# pmod-level-conv.net
KiCad netlist of a schematic drawn in EAGLE
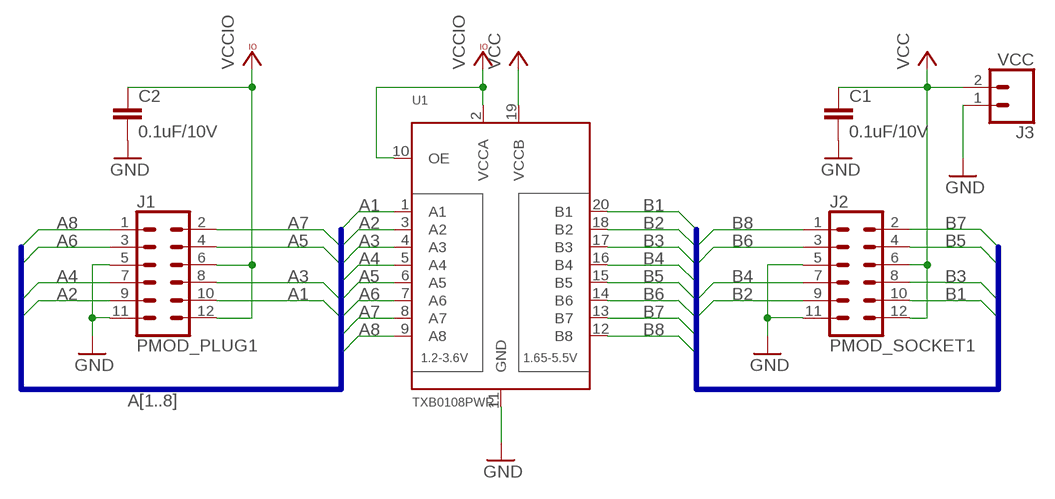
[diagram p0: schematic, sheet 1]

(export (version "E")
  (design (tool "Eeschema 10.0.6"))
  (components
    (comp (ref "C1")
      (value "0.1uF/10V")
      (footprint "eagle-import:C0603K")
      (libsource (lib "eagle-import") (part "C-EUC0603K"))
    )
    (comp (ref "C2")
      (value "0.1uF/10V")
      (footprint "eagle-import:C0603K")
      (libsource (lib "eagle-import") (part "C-EUC0603K"))
    )
    (comp (ref "J1")
      (value "PMOD_PLUG1")
      (footprint "eagle-import:2X6_SMD_RA_PLUG")
      (libsource (lib "eagle-import") (part "CONN_06X2SMD_RA_PLUG"))
    )
    (comp (ref "J2")
      (value "PMOD_SOCKET1")
      (footprint "eagle-import:2X6_SMD_RA_SOCKET")
      (libsource (lib "eagle-import") (part "CONN_06X2SMD_RA_SOCKET"))
    )
    (comp (ref "J3")
      (value "VCC")
      (footprint "eagle-import:JST-2-SMD")
      (libsource (lib "eagle-import") (part "CONN_02-JST-2MM-SMT"))
    )
    (comp (ref "U1")
      (value "TXB0108PWR")
      (footprint "eagle-import:TSSOP20")
      (libsource (lib "eagle-import") (part "TXB0108PWR"))
    )
  )
  (nets
    (net (code "1") (name "/A1") (class "Default")
      (node (ref "J1") (pin "10") (pinfunction "10_10") (pintype "passive"))
      (node (ref "U1") (pin "1") (pinfunction "A1_1") (pintype "bidirectional"))
    )
    (net (code "2") (name "/A2") (class "Default")
      (node (ref "J1") (pin "9") (pinfunction "9_9") (pintype "passive"))
      (node (ref "U1") (pin "3") (pinfunction "A2_3") (pintype "bidirectional"))
    )
    (net (code "3") (name "/A3") (class "Default")
      (node (ref "J1") (pin "8") (pinfunction "8_8") (pintype "passive"))
      (node (ref "U1") (pin "4") (pinfunction "A3_4") (pintype "bidirectional"))
    )
    (net (code "4") (name "/A4") (class "Default")
      (node (ref "J1") (pin "7") (pinfunction "7_7") (pintype "passive"))
      (node (ref "U1") (pin "5") (pinfunction "A4_5") (pintype "bidirectional"))
    )
    (net (code "5") (name "/A5") (class "Default")
      (node (ref "J1") (pin "4") (pinfunction "4_4") (pintype "passive"))
      (node (ref "U1") (pin "6") (pinfunction "A5_6") (pintype "bidirectional"))
    )
    (net (code "6") (name "/A6") (class "Default")
      (node (ref "J1") (pin "3") (pinfunction "3_3") (pintype "passive"))
      (node (ref "U1") (pin "7") (pinfunction "A6_7") (pintype "bidirectional"))
    )
    (net (code "7") (name "/A7") (class "Default")
      (node (ref "J1") (pin "2") (pinfunction "2_2") (pintype "passive"))
      (node (ref "U1") (pin "8") (pinfunction "A7_8") (pintype "bidirectional"))
    )
    (net (code "8") (name "/A8") (class "Default")
      (node (ref "J1") (pin "1") (pinfunction "1_1") (pintype "passive"))
      (node (ref "U1") (pin "9") (pinfunction "A8_9") (pintype "bidirectional"))
    )
    (net (code "10") (name "/B1") (class "Default")
      (node (ref "J2") (pin "10") (pinfunction "10_10") (pintype "passive"))
      (node (ref "U1") (pin "20") (pinfunction "B1_20") (pintype "bidirectional"))
    )
    (net (code "11") (name "/B2") (class "Default")
      (node (ref "J2") (pin "9") (pinfunction "9_9") (pintype "passive"))
      (node (ref "U1") (pin "18") (pinfunction "B2_18") (pintype "bidirectional"))
    )
    (net (code "12") (name "/B3") (class "Default")
      (node (ref "J2") (pin "8") (pinfunction "8_8") (pintype "passive"))
      (node (ref "U1") (pin "17") (pinfunction "B3_17") (pintype "bidirectional"))
    )
    (net (code "13") (name "/B4") (class "Default")
      (node (ref "J2") (pin "7") (pinfunction "7_7") (pintype "passive"))
      (node (ref "U1") (pin "16") (pinfunction "B4_16") (pintype "bidirectional"))
    )
    (net (code "14") (name "/B5") (class "Default")
      (node (ref "J2") (pin "4") (pinfunction "4_4") (pintype "passive"))
      (node (ref "U1") (pin "15") (pinfunction "B5_15") (pintype "bidirectional"))
    )
    (net (code "15") (name "/B6") (class "Default")
      (node (ref "J2") (pin "3") (pinfunction "3_3") (pintype "passive"))
      (node (ref "U1") (pin "14") (pinfunction "B6_14") (pintype "bidirectional"))
    )
    (net (code "16") (name "/B7") (class "Default")
      (node (ref "J2") (pin "2") (pinfunction "2_2") (pintype "passive"))
      (node (ref "U1") (pin "13") (pinfunction "B7_13") (pintype "bidirectional"))
    )
    (net (code "17") (name "/B8") (class "Default")
      (node (ref "J2") (pin "1") (pinfunction "1_1") (pintype "passive"))
      (node (ref "U1") (pin "12") (pinfunction "B8_12") (pintype "bidirectional"))
    )
    (net (code "18") (name "GND") (class "Default")
      (node (ref "C1") (pin "2") (pinfunction "2_2") (pintype "passive"))
      (node (ref "C2") (pin "2") (pinfunction "2_2") (pintype "passive"))
      (node (ref "J1") (pin "11") (pinfunction "11_11") (pintype "passive"))
      (node (ref "J1") (pin "5") (pinfunction "5_5") (pintype "passive"))
      (node (ref "J2") (pin "11") (pinfunction "11_11") (pintype "passive"))
      (node (ref "J2") (pin "5") (pinfunction "5_5") (pintype "passive"))
      (node (ref "J3") (pin "1") (pinfunction "2_1") (pintype "passive"))
      (node (ref "U1") (pin "11") (pinfunction "GND_11") (pintype "bidirectional"))
    )
    (net (code "19") (name "VCC") (class "Default")
      (node (ref "C1") (pin "1") (pinfunction "1_1") (pintype "passive"))
      (node (ref "J2") (pin "12") (pinfunction "12_12") (pintype "passive"))
      (node (ref "J2") (pin "6") (pinfunction "6_6") (pintype "passive"))
      (node (ref "J3") (pin "2") (pinfunction "1_2") (pintype "passive"))
      (node (ref "U1") (pin "19") (pinfunction "VCCB_19") (pintype "bidirectional"))
    )
    (net (code "20") (name "VCCIO") (class "Default")
      (node (ref "C2") (pin "1") (pinfunction "1_1") (pintype "passive"))
      (node (ref "J1") (pin "12") (pinfunction "12_12") (pintype "passive"))
      (node (ref "J1") (pin "6") (pinfunction "6_6") (pintype "passive"))
      (node (ref "U1") (pin "10") (pinfunction "OE_10") (pintype "bidirectional"))
      (node (ref "U1") (pin "2") (pinfunction "VCCA_2") (pintype "bidirectional"))
    )
  )
)
